# MB1280.net
KiCad netlist of a schematic drawn in Altium Designer
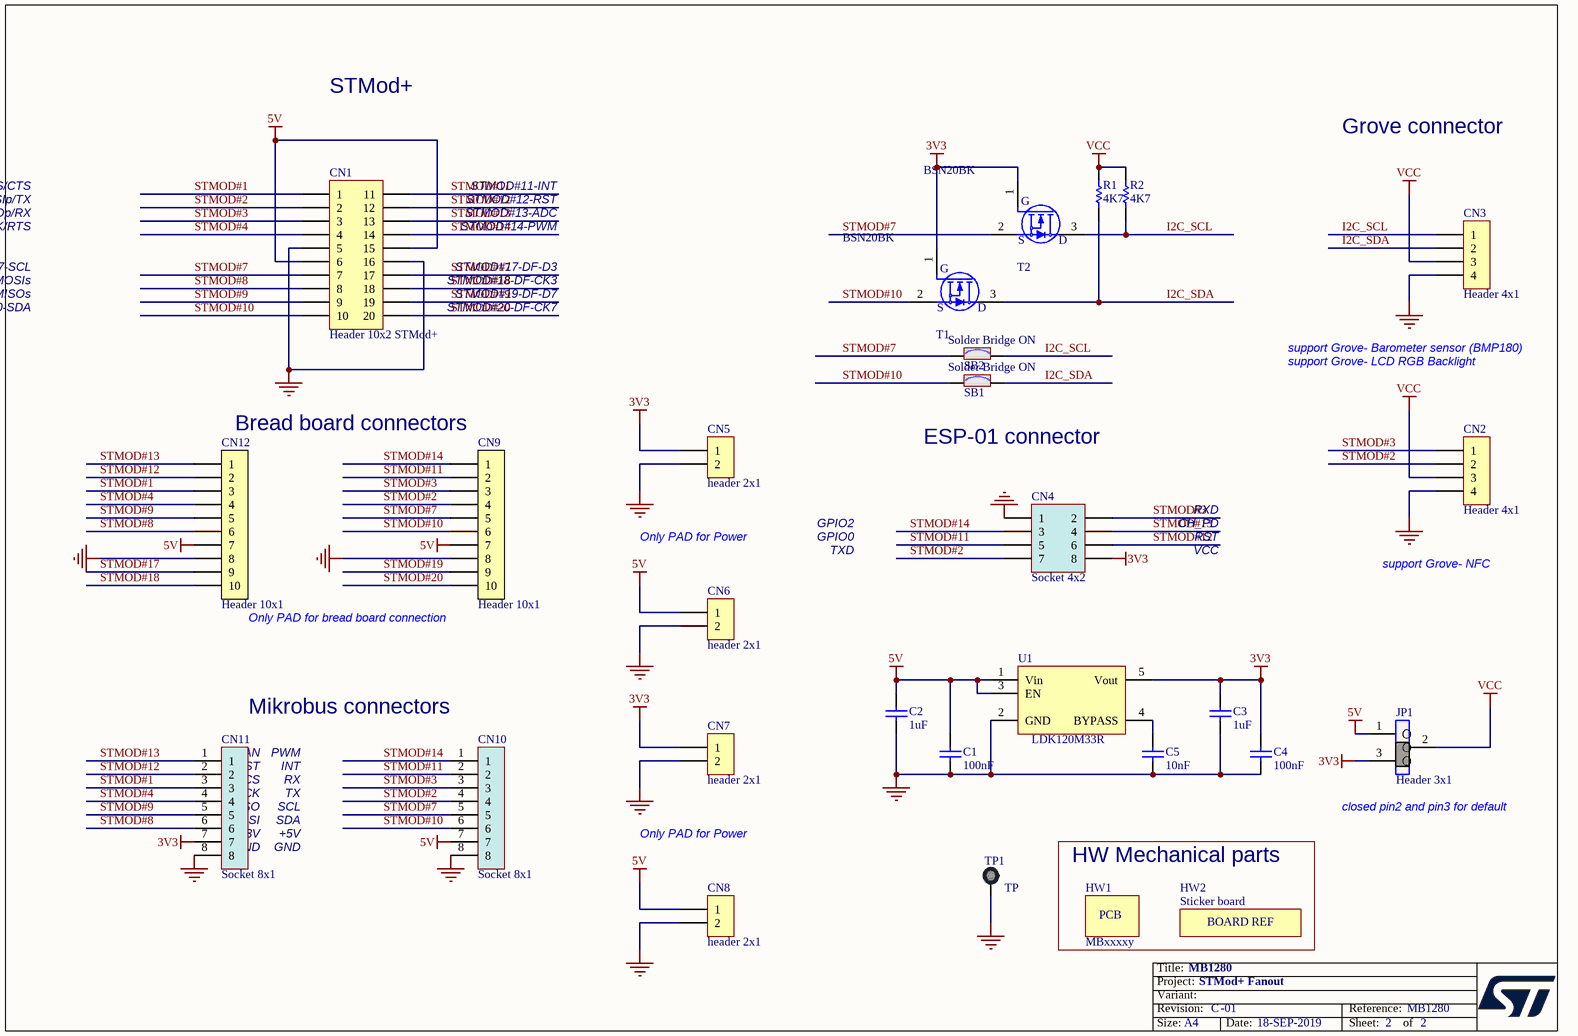
[diagram p0: MB1280.SchDoc]

(export (version "E")
  (design (tool "Eeschema 10.0.6"))
  (components
    (comp (ref "C1")
      (value "100nF")
      (footprint "C0603")
      (description "Capacitor, MLCC, 100nF, 16V, X7R, 10%, 0603, T=0,8mm")
      (fields
        (field (name "INTERNAL_PART_NUMBER") "MCD-00211")
        (field (name "MANUFACTURER_PART_NUMBER") "CC0603KRX7R7BB104")
        (field (name "PROVIDED_BY") "SUBCO")
      )
      (libsource (lib "MCD_PARTS_database") (part "Capacitor"))
    )
    (comp (ref "C2")
      (value "1uF")
      (footprint "C0603_H0P8")
      (description "Capacitor,1uF,50V,X5R,10%,0603, T=0.8mm")
      (fields
        (field (name "INTERNAL_PART_NUMBER") "MCD-01703")
        (field (name "MANUFACTURER_PART_NUMBER") "CC0603KRX5R9BB105")
        (field (name "PROVIDED_BY") "SUBCO")
      )
      (libsource (lib "MCD_PARTS_database") (part "Capacitor"))
    )
    (comp (ref "C3")
      (value "1uF")
      (footprint "C0603_H0P8")
      (description "Capacitor,1uF,50V,X5R,10%,0603, T=0.8mm")
      (fields
        (field (name "INTERNAL_PART_NUMBER") "MCD-01703")
        (field (name "MANUFACTURER_PART_NUMBER") "CC0603KRX5R9BB105")
        (field (name "PROVIDED_BY") "SUBCO")
      )
      (libsource (lib "MCD_PARTS_database") (part "Capacitor"))
    )
    (comp (ref "C4")
      (value "100nF")
      (footprint "C0603")
      (description "Capacitor, MLCC, 100nF, 16V, X7R, 10%, 0603, T=0,8mm")
      (fields
        (field (name "INTERNAL_PART_NUMBER") "MCD-00211")
        (field (name "MANUFACTURER_PART_NUMBER") "CC0603KRX7R7BB104")
        (field (name "PROVIDED_BY") "SUBCO")
      )
      (libsource (lib "MCD_PARTS_database") (part "Capacitor"))
    )
    (comp (ref "C5")
      (value "10nF")
      (footprint "C0603")
      (description "Capacitor, MLCC, 10nF, 50V, X7R, 10%, 0603, T=0.8mm")
      (fields
        (field (name "INTERNAL_PART_NUMBER") "MCD-00017")
        (field (name "MANUFACTURER_PART_NUMBER") "CC0603KRX7R9BB103")
        (field (name "PROVIDED_BY") "SUBCO")
      )
      (libsource (lib "MCD_PARTS_database") (part "Capacitor"))
    )
    (comp (ref "CN1")
      (value "Header 10x2 STMod+")
      (footprint "CON_SAMTEC_TMM-110-01-L-D-RA__STMOD+")
      (description "Header 10x2, 2mm, RA, TH, Height 3.20mm/3.50mm")
      (fields
        (field (name "INTERNAL_PART_NUMBER") "MCD-00288")
        (field (name "MANUFACTURER_PART_NUMBER") "TMM-110-01-L-D-RA")
        (field (name "PROVIDED_BY") "SUBCO")
      )
      (libsource (lib "MCD_PARTS_database") (part "Header 10x2 STMod+"))
    )
    (comp (ref "CN2")
      (value "Header 4x1")
      (footprint "CON_988-JIUBABA_A2006LF-04A")
      (description "Header 4x1, 2mm, VR, SMT")
      (fields
        (field (name "INTERNAL_PART_NUMBER") "MCD-01741")
        (field (name "MANUFACTURER_PART_NUMBER") "A2006LF-04A")
        (field (name "PROVIDED_BY") "SUBCO")
      )
      (libsource (lib "MCD_PARTS_database") (part "Header 4x1"))
    )
    (comp (ref "CN3")
      (value "Header 4x1")
      (footprint "CON_988-JIUBABA_A2006LF-04A")
      (description "Header 4x1, 2mm, VR, SMT")
      (fields
        (field (name "INTERNAL_PART_NUMBER") "MCD-01741")
        (field (name "MANUFACTURER_PART_NUMBER") "A2006LF-04A")
        (field (name "PROVIDED_BY") "SUBCO")
      )
      (libsource (lib "MCD_PARTS_database") (part "Header 4x1"))
    )
    (comp (ref "CN4")
      (value "Socket 4x2")
      (footprint "CON_SAMTEC_SSW-104-01-X-D")
      (description "Socket 4x2,2.54mm,VR,TH, height 8.51/2.64mm")
      (fields
        (field (name "INTERNAL_PART_NUMBER") "MCD-01742")
        (field (name "MANUFACTURER_PART_NUMBER") "SSW-104-01-G-D")
        (field (name "PROVIDED_BY") "SUBCO")
      )
      (libsource (lib "MCD_PARTS_database") (part "Socket 4x2"))
    )
    (comp (ref "CN5")
      (value "header 2x1")
      (footprint "CON_988-JIUBABA_PHFS25-11-02-G0B115-T-1")
      (description "Header, 2x1, 2.54mm, VR, TH, Height 6mm/3mm")
      (fields
        (field (name "INTERNAL_PART_NUMBER") "MCD-00314")
        (field (name "MANUFACTURER_PART_NUMBER") "PHFS25-11-02-G0B115-T-1")
        (field (name "PROVIDED_BY") "SUBCO")
      )
      (libsource (lib "MCD_PARTS_database") (part "Header 2x1"))
    )
    (comp (ref "CN6")
      (value "header 2x1")
      (footprint "CON_988-JIUBABA_PHFS25-11-02-G0B115-T-1")
      (description "Header, 2x1, 2.54mm, VR, TH, Height 6mm/3mm")
      (fields
        (field (name "INTERNAL_PART_NUMBER") "MCD-00314")
        (field (name "MANUFACTURER_PART_NUMBER") "PHFS25-11-02-G0B115-T-1")
        (field (name "PROVIDED_BY") "SUBCO")
      )
      (libsource (lib "MCD_PARTS_database") (part "Header 2x1"))
    )
    (comp (ref "CN7")
      (value "header 2x1")
      (footprint "CON_988-JIUBABA_PHFS25-11-02-G0B115-T-1")
      (description "Header, 2x1, 2.54mm, VR, TH, Height 6mm/3mm")
      (fields
        (field (name "INTERNAL_PART_NUMBER") "MCD-00314")
        (field (name "MANUFACTURER_PART_NUMBER") "PHFS25-11-02-G0B115-T-1")
        (field (name "PROVIDED_BY") "SUBCO")
      )
      (libsource (lib "MCD_PARTS_database") (part "Header 2x1"))
    )
    (comp (ref "CN8")
      (value "header 2x1")
      (footprint "CON_988-JIUBABA_PHFS25-11-02-G0B115-T-1")
      (description "Header, 2x1, 2.54mm, VR, TH, Height 6mm/3mm")
      (fields
        (field (name "INTERNAL_PART_NUMBER") "MCD-00314")
        (field (name "MANUFACTURER_PART_NUMBER") "PHFS25-11-02-G0B115-T-1")
        (field (name "PROVIDED_BY") "SUBCO")
      )
      (libsource (lib "MCD_PARTS_database") (part "Header 2x1"))
    )
    (comp (ref "CN9")
      (value "Header 10x1")
      (footprint "CON_SAMTEC_TSW-110-14-G-S")
      (description "Header 10x1, 2,54mm height  10.67mm")
      (fields
        (field (name "INTERNAL_PART_NUMBER") "MCD-01591")
        (field (name "MANUFACTURER_PART_NUMBER") "TSW-110-14-G-S")
        (field (name "PROVIDED_BY") "SUBCO")
      )
      (libsource (lib "MCD_PARTS_database") (part "Header 10x1"))
    )
    (comp (ref "CN10")
      (value "Socket 8x1")
      (footprint "CON_SAMTEC_SSW-108-01-X-S")
      (description "Socket 8x1, 2.54mm, VR, TH, height 8.51/2.64mm")
      (fields
        (field (name "INTERNAL_PART_NUMBER") "MCD-01743")
        (field (name "MANUFACTURER_PART_NUMBER") "SSW-108-01-G-S")
      )
      (libsource (lib "MCD_PARTS_database") (part "Socket 8x1"))
    )
    (comp (ref "CN11")
      (value "Socket 8x1")
      (footprint "CON_SAMTEC_SSW-108-01-X-S")
      (description "Socket 8x1, 2.54mm, VR, TH, height 8.51/2.64mm")
      (fields
        (field (name "INTERNAL_PART_NUMBER") "MCD-01743")
        (field (name "MANUFACTURER_PART_NUMBER") "SSW-108-01-G-S")
      )
      (libsource (lib "MCD_PARTS_database") (part "Socket 8x1"))
    )
    (comp (ref "CN12")
      (value "Header 10x1")
      (footprint "CON_SAMTEC_TSW-110-14-G-S")
      (description "Header 10x1, 2,54mm height  10.67mm")
      (fields
        (field (name "INTERNAL_PART_NUMBER") "MCD-01591")
        (field (name "MANUFACTURER_PART_NUMBER") "TSW-110-14-G-S")
        (field (name "PROVIDED_BY") "SUBCO")
      )
      (libsource (lib "MCD_PARTS_database") (part "Header 10x1"))
    )
    (comp (ref "HW1")
      (value "MBxxxxy")
      (description "PCB, xxxx for PCB number, Y for PCB revision")
      (fields
        (field (name "INTERNAL_PART_NUMBER") "MCD-00216")
        (field (name "MANUFACTURER_PART_NUMBER") "n/a")
        (field (name "PROVIDED_BY") "SUBCO")
      )
      (libsource (lib "MCD_PARTS_database") (part "PCB"))
    )
    (comp (ref "HW2")
      (value "Sticker board")
      (footprint "STICKER_25X9")
      (description "Sticker to mention board reference + serial number")
      (fields
        (field (name "INTERNAL_PART_NUMBER") "MCD-00235")
        (field (name "MANUFACTURER_PART_NUMBER") "n/a")
        (field (name "PROVIDED_BY") "SUBCO")
      )
      (libsource (lib "MCD_PARTS_database") (part "STICKER_BOARD_REF"))
    )
    (comp (ref "JP1")
      (value "Header 3x1")
      (footprint "CON_SAMTEC_TSW-103-07-F-S")
      (description "Header, 3x1, 2,54mm, VR, TH, Height 5.84mm/2.54mm - Shunt Fitted 2-3 by default")
      (fields
        (field (name "INTERNAL_PART_NUMBER") "MCD-00685")
        (field (name "MANUFACTURER_PART_NUMBER") "TSW-103-07-F-S")
        (field (name "PROVIDED_BY") "SUBCO")
      )
      (libsource (lib "MCD_PARTS_database") (part "Jumper_Header 3x1 Fitted 2-3"))
    )
    (comp (ref "R1")
      (value "4K7")
      (footprint "R0603")
      (description "Resistor,4K7,0603,1%,1/10W")
      (fields
        (field (name "INTERNAL_PART_NUMBER") "MCD-00219")
        (field (name "MANUFACTURER_PART_NUMBER") "RC0603FR-074K7L")
        (field (name "PROVIDED_BY") "SUBCO")
      )
      (libsource (lib "MCD_PARTS_database") (part "Resistor"))
    )
    (comp (ref "R2")
      (value "4K7")
      (footprint "R0603")
      (description "Resistor,4K7,0603,1%,1/10W")
      (fields
        (field (name "INTERNAL_PART_NUMBER") "MCD-00219")
        (field (name "MANUFACTURER_PART_NUMBER") "RC0603FR-074K7L")
        (field (name "PROVIDED_BY") "SUBCO")
      )
      (libsource (lib "MCD_PARTS_database") (part "Resistor"))
    )
    (comp (ref "SB1")
      (value "Solder Bridge ON")
      (footprint "SOLDER-BRIDGE_R0603-0R")
      (fields
        (field (name "INTERNAL_PART_NUMBER") "MCD-00071")
        (field (name "MANUFACTURER_PART_NUMBER") "RC0603JR-070RL")
        (field (name "MANUFACTURER") "YAGEO")
        (field (name "PROVIDED_BY") "SUBCO")
      )
      (libsource (lib "MCD_PARTS_database") (part "SB_ON"))
    )
    (comp (ref "SB2")
      (value "Solder Bridge ON")
      (footprint "SOLDER-BRIDGE_R0603-0R")
      (fields
        (field (name "INTERNAL_PART_NUMBER") "MCD-00071")
        (field (name "MANUFACTURER_PART_NUMBER") "RC0603JR-070RL")
        (field (name "MANUFACTURER") "YAGEO")
        (field (name "PROVIDED_BY") "SUBCO")
      )
      (libsource (lib "MCD_PARTS_database") (part "SB_ON"))
    )
    (comp (ref "T1")
      (value "BSN20BK")
      (footprint "MOS_SOT23")
      (description "N-channel enhancement mode field-effect transistor")
      (fields
        (field (name "INTERNAL_PART_NUMBER") "MCD-01969")
        (field (name "MANUFACTURER") "Nexperia")
        (field (name "PROVIDED_BY") "SUBCO")
      )
      (libsource (lib "MCD_PARTS_database") (part "BSN20"))
    )
    (comp (ref "T2")
      (value "BSN20BK")
      (footprint "MOS_SOT23")
      (description "N-channel enhancement mode field-effect transistor")
      (fields
        (field (name "INTERNAL_PART_NUMBER") "MCD-01969")
        (field (name "MANUFACTURER") "Nexperia")
        (field (name "PROVIDED_BY") "SUBCO")
      )
      (libsource (lib "MCD_PARTS_database") (part "BSN20"))
    )
    (comp (ref "TP1")
      (value "TP")
      (footprint "TP_PTH_1MM_2MM")
      (description "Test Point trought hole 1mm/2mm")
      (fields
        (field (name "INTERNAL_PART_NUMBER") "MCD-01506")
        (field (name "Comment") "Test_Point_PTH_1mm_2mm")
      )
      (libsource (lib "MCD_PARTS_database") (part "Test_Point_PTH_1mm_2mm"))
    )
    (comp (ref "U1")
      (value "LDK120M33R")
      (footprint "REG_SOT23-5L")
      (description "200 mA low quiescent current very low noise LDO")
      (fields
        (field (name "INTERNAL_PART_NUMBER") "MCD-00663")
        (field (name "MANUFACTURER") "STMICROELECTRONICS")
        (field (name "PROVIDED_BY") "SUBCO with ST control")
      )
      (libsource (lib "MCD_PARTS_database") (part "LDK120M33R"))
    )
  )
  (nets
    (net (code "1") (name "/I2C_SCL") (class "Default")
      (node (ref "CN3") (pin "1") (pinfunction "1_1") (pintype "passive"))
      (node (ref "R2") (pin "2") (pinfunction "2_2") (pintype "passive"))
      (node (ref "SB2") (pin "2") (pinfunction "2_2") (pintype "passive"))
      (node (ref "T2") (pin "3") (pinfunction "D_3") (pintype "passive"))
    )
    (net (code "2") (name "/I2C_SDA") (class "Default")
      (node (ref "CN3") (pin "2") (pinfunction "2_2") (pintype "passive"))
      (node (ref "R1") (pin "2") (pinfunction "2_2") (pintype "passive"))
      (node (ref "SB1") (pin "2") (pinfunction "2_2") (pintype "passive"))
      (node (ref "T1") (pin "3") (pinfunction "D_3") (pintype "passive"))
    )
    (net (code "3") (name "/STMOD#1") (class "Default")
      (node (ref "CN1") (pin "1") (pinfunction "1_1") (pintype "passive"))
      (node (ref "CN11") (pin "3") (pinfunction "3_3") (pintype "passive"))
      (node (ref "CN12") (pin "3") (pinfunction "3_3") (pintype "passive"))
    )
    (net (code "4") (name "/STMOD#2") (class "Default")
      (node (ref "CN1") (pin "2") (pinfunction "2_2") (pintype "passive"))
      (node (ref "CN10") (pin "4") (pinfunction "4_4") (pintype "passive"))
      (node (ref "CN2") (pin "2") (pinfunction "2_2") (pintype "passive"))
      (node (ref "CN4") (pin "7") (pinfunction "7_7") (pintype "passive"))
      (node (ref "CN9") (pin "4") (pinfunction "4_4") (pintype "passive"))
    )
    (net (code "5") (name "/STMOD#3") (class "Default")
      (node (ref "CN1") (pin "3") (pinfunction "3_3") (pintype "passive"))
      (node (ref "CN10") (pin "3") (pinfunction "3_3") (pintype "passive"))
      (node (ref "CN2") (pin "1") (pinfunction "1_1") (pintype "passive"))
      (node (ref "CN4") (pin "2") (pinfunction "2_2") (pintype "passive"))
      (node (ref "CN9") (pin "3") (pinfunction "3_3") (pintype "passive"))
    )
    (net (code "6") (name "/STMOD#4") (class "Default")
      (node (ref "CN1") (pin "4") (pinfunction "4_4") (pintype "passive"))
      (node (ref "CN11") (pin "4") (pinfunction "4_4") (pintype "passive"))
      (node (ref "CN12") (pin "4") (pinfunction "4_4") (pintype "passive"))
    )
    (net (code "7") (name "/STMOD#7") (class "Default")
      (node (ref "CN1") (pin "7") (pinfunction "7_7") (pintype "passive"))
      (node (ref "CN10") (pin "5") (pinfunction "5_5") (pintype "passive"))
      (node (ref "CN9") (pin "5") (pinfunction "5_5") (pintype "passive"))
      (node (ref "SB2") (pin "1") (pinfunction "1_1") (pintype "passive"))
      (node (ref "T2") (pin "2") (pinfunction "S_2") (pintype "passive"))
    )
    (net (code "8") (name "/STMOD#8") (class "Default")
      (node (ref "CN1") (pin "8") (pinfunction "8_8") (pintype "passive"))
      (node (ref "CN11") (pin "6") (pinfunction "6_6") (pintype "passive"))
      (node (ref "CN12") (pin "6") (pinfunction "6_6") (pintype "passive"))
    )
    (net (code "9") (name "/STMOD#9") (class "Default")
      (node (ref "CN1") (pin "9") (pinfunction "9_9") (pintype "passive"))
      (node (ref "CN11") (pin "5") (pinfunction "5_5") (pintype "passive"))
      (node (ref "CN12") (pin "5") (pinfunction "5_5") (pintype "passive"))
    )
    (net (code "10") (name "/STMOD#10") (class "Default")
      (node (ref "CN1") (pin "10") (pinfunction "10_10") (pintype "passive"))
      (node (ref "CN10") (pin "6") (pinfunction "6_6") (pintype "passive"))
      (node (ref "CN9") (pin "6") (pinfunction "6_6") (pintype "passive"))
      (node (ref "SB1") (pin "1") (pinfunction "1_1") (pintype "passive"))
      (node (ref "T1") (pin "2") (pinfunction "S_2") (pintype "passive"))
    )
    (net (code "11") (name "/STMOD#11") (class "Default")
      (node (ref "CN1") (pin "11") (pinfunction "11_11") (pintype "passive"))
      (node (ref "CN10") (pin "2") (pinfunction "2_2") (pintype "passive"))
      (node (ref "CN4") (pin "5") (pinfunction "5_5") (pintype "passive"))
      (node (ref "CN9") (pin "2") (pinfunction "2_2") (pintype "passive"))
    )
    (net (code "12") (name "/STMOD#12") (class "Default")
      (node (ref "CN1") (pin "12") (pinfunction "12_12") (pintype "passive"))
      (node (ref "CN11") (pin "2") (pinfunction "2_2") (pintype "passive"))
      (node (ref "CN12") (pin "2") (pinfunction "2_2") (pintype "passive"))
      (node (ref "CN4") (pin "6") (pinfunction "6_6") (pintype "passive"))
    )
    (net (code "13") (name "/STMOD#13") (class "Default")
      (node (ref "CN1") (pin "13") (pinfunction "13_13") (pintype "passive"))
      (node (ref "CN11") (pin "1") (pinfunction "1_1") (pintype "passive"))
      (node (ref "CN12") (pin "1") (pinfunction "1_1") (pintype "passive"))
      (node (ref "CN4") (pin "4") (pinfunction "4_4") (pintype "passive"))
    )
    (net (code "14") (name "/STMOD#14") (class "Default")
      (node (ref "CN1") (pin "14") (pinfunction "14_14") (pintype "passive"))
      (node (ref "CN10") (pin "1") (pinfunction "1_1") (pintype "passive"))
      (node (ref "CN4") (pin "3") (pinfunction "3_3") (pintype "passive"))
      (node (ref "CN9") (pin "1") (pinfunction "1_1") (pintype "passive"))
    )
    (net (code "15") (name "/STMOD#17") (class "Default")
      (node (ref "CN1") (pin "17") (pinfunction "17_17") (pintype "passive"))
      (node (ref "CN12") (pin "9") (pinfunction "9_9") (pintype "passive"))
    )
    (net (code "16") (name "/STMOD#18") (class "Default")
      (node (ref "CN1") (pin "18") (pinfunction "18_18") (pintype "passive"))
      (node (ref "CN12") (pin "10") (pinfunction "10_10") (pintype "passive"))
    )
    (net (code "17") (name "/STMOD#19") (class "Default")
      (node (ref "CN1") (pin "19") (pinfunction "19_19") (pintype "passive"))
      (node (ref "CN9") (pin "9") (pinfunction "9_9") (pintype "passive"))
    )
    (net (code "18") (name "/STMOD#20") (class "Default")
      (node (ref "CN1") (pin "20") (pinfunction "20_20") (pintype "passive"))
      (node (ref "CN9") (pin "10") (pinfunction "10_10") (pintype "passive"))
    )
    (net (code "19") (name "3V3") (class "Default")
      (node (ref "C3") (pin "2") (pinfunction "2_2") (pintype "passive"))
      (node (ref "C4") (pin "2") (pinfunction "2_2") (pintype "passive"))
      (node (ref "CN11") (pin "7") (pinfunction "7_7") (pintype "passive"))
      (node (ref "CN4") (pin "8") (pinfunction "8_8") (pintype "passive"))
      (node (ref "CN5") (pin "1") (pinfunction "1_1") (pintype "passive"))
      (node (ref "CN7") (pin "1") (pinfunction "1_1") (pintype "passive"))
      (node (ref "JP1") (pin "3") (pinfunction "3_3") (pintype "passive"))
      (node (ref "T1") (pin "1") (pinfunction "G_1") (pintype "passive"))
      (node (ref "T2") (pin "1") (pinfunction "G_1") (pintype "passive"))
      (node (ref "U1") (pin "5") (pinfunction "Vout_5") (pintype "power_in"))
    )
    (net (code "20") (name "5V") (class "Default")
      (node (ref "C1") (pin "2") (pinfunction "2_2") (pintype "passive"))
      (node (ref "C2") (pin "2") (pinfunction "2_2") (pintype "passive"))
      (node (ref "CN1") (pin "15") (pinfunction "15_15") (pintype "passive"))
      (node (ref "CN1") (pin "6") (pinfunction "6_6") (pintype "passive"))
      (node (ref "CN10") (pin "7") (pinfunction "7_7") (pintype "passive"))
      (node (ref "CN12") (pin "7") (pinfunction "7_7") (pintype "passive"))
      (node (ref "CN6") (pin "1") (pinfunction "1_1") (pintype "passive"))
      (node (ref "CN8") (pin "1") (pinfunction "1_1") (pintype "passive"))
      (node (ref "CN9") (pin "7") (pinfunction "7_7") (pintype "passive"))
      (node (ref "JP1") (pin "1") (pinfunction "1_1") (pintype "passive"))
      (node (ref "U1") (pin "1") (pinfunction "Vin_1") (pintype "power_in"))
      (node (ref "U1") (pin "3") (pinfunction "EN_3") (pintype "passive"))
    )
    (net (code "21") (name "GND") (class "Default")
      (node (ref "C1") (pin "1") (pinfunction "1_1") (pintype "passive"))
      (node (ref "C2") (pin "1") (pinfunction "1_1") (pintype "passive"))
      (node (ref "C3") (pin "1") (pinfunction "1_1") (pintype "passive"))
      (node (ref "C4") (pin "1") (pinfunction "1_1") (pintype "passive"))
      (node (ref "C5") (pin "1") (pinfunction "1_1") (pintype "passive"))
      (node (ref "CN1") (pin "16") (pinfunction "16_16") (pintype "passive"))
      (node (ref "CN1") (pin "5") (pinfunction "5_5") (pintype "passive"))
      (node (ref "CN10") (pin "8") (pinfunction "8_8") (pintype "passive"))
      (node (ref "CN11") (pin "8") (pinfunction "8_8") (pintype "passive"))
      (node (ref "CN12") (pin "8") (pinfunction "8_8") (pintype "passive"))
      (node (ref "CN2") (pin "4") (pinfunction "4_4") (pintype "passive"))
      (node (ref "CN3") (pin "4") (pinfunction "4_4") (pintype "passive"))
      (node (ref "CN4") (pin "1") (pinfunction "1_1") (pintype "passive"))
      (node (ref "CN5") (pin "2") (pinfunction "2_2") (pintype "passive"))
      (node (ref "CN6") (pin "2") (pinfunction "2_2") (pintype "passive"))
      (node (ref "CN7") (pin "2") (pinfunction "2_2") (pintype "passive"))
      (node (ref "CN8") (pin "2") (pinfunction "2_2") (pintype "passive"))
      (node (ref "CN9") (pin "8") (pinfunction "8_8") (pintype "passive"))
      (node (ref "TP1") (pin "1") (pinfunction "1_1") (pintype "passive"))
      (node (ref "U1") (pin "2") (pinfunction "GND_2") (pintype "passive"))
    )
    (net (code "22") (name "Net-(U1-BYPASS)") (class "Default")
      (node (ref "C5") (pin "2") (pinfunction "2_2") (pintype "passive"))
      (node (ref "U1") (pin "4") (pinfunction "BYPASS_4") (pintype "passive"))
    )
    (net (code "23") (name "VCC") (class "Default")
      (node (ref "CN2") (pin "3") (pinfunction "3_3") (pintype "passive"))
      (node (ref "CN3") (pin "3") (pinfunction "3_3") (pintype "passive"))
      (node (ref "JP1") (pin "2") (pinfunction "2_2") (pintype "passive"))
      (node (ref "R1") (pin "1") (pinfunction "1_1") (pintype "passive"))
      (node (ref "R2") (pin "1") (pinfunction "1_1") (pintype "passive"))
    )
  )
)
